# McPiFace-60mmFan-V3.net
KiCad netlist of a schematic drawn in EAGLE
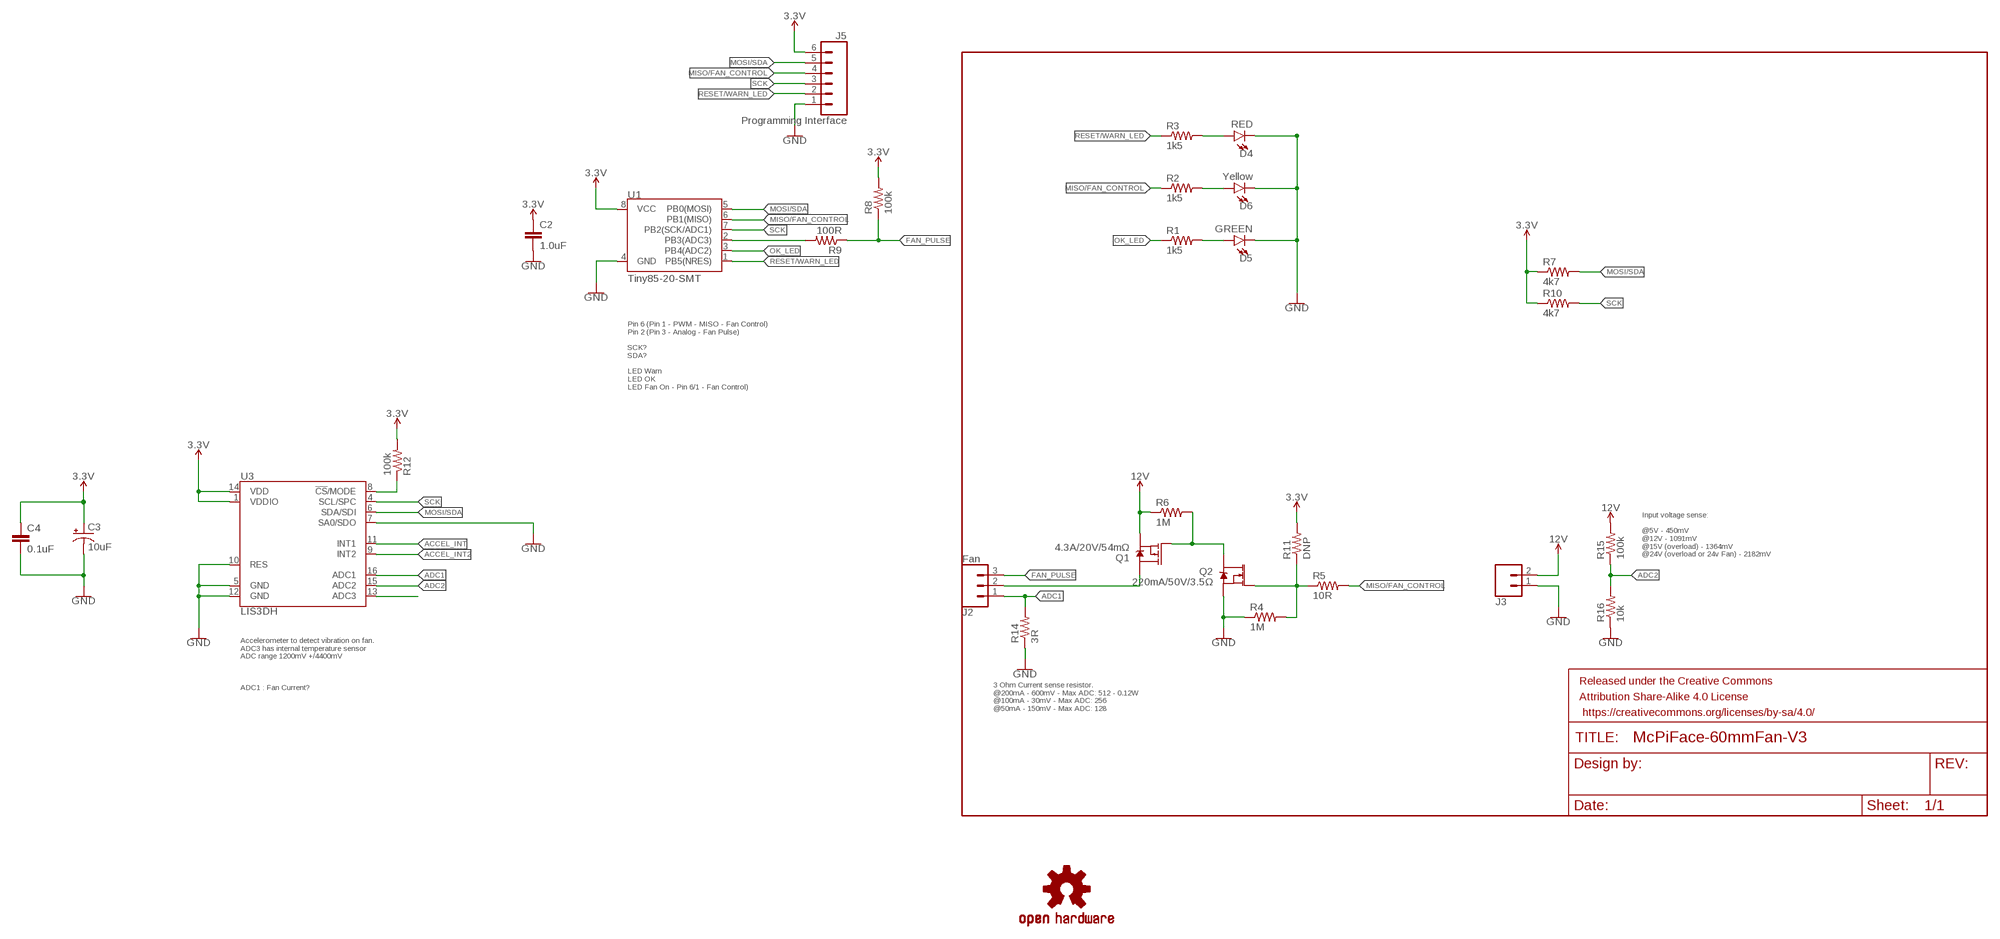
[diagram p0: schematic, sheet 1]

(export (version "E")
  (design (tool "Eeschema 10.0.6"))
  (components
    (comp (ref "C2")
      (value "1.0uF")
      (footprint "eagle-import:0805")
      (libsource (lib "eagle-import") (part "1.0UF-0805-25V-10%"))
    )
    (comp (ref "C3")
      (value "10uF")
      (footprint "eagle-import:EIA3216")
      (libsource (lib "eagle-import") (part "10UF-16V-10%(TANT)"))
    )
    (comp (ref "C4")
      (value "0.1uF")
      (footprint "eagle-import:0805")
      (libsource (lib "eagle-import") (part "1.0UF-0805-25V-10%"))
    )
    (comp (ref "D4")
      (value "RED")
      (footprint "eagle-import:LED-1206")
      (libsource (lib "eagle-import") (part "LED-RED1206"))
    )
    (comp (ref "D5")
      (value "GREEN")
      (footprint "eagle-import:LED-1206")
      (libsource (lib "eagle-import") (part "LED-GREEN1206"))
    )
    (comp (ref "D6")
      (value "Yellow")
      (footprint "eagle-import:LED-1206")
      (libsource (lib "eagle-import") (part "LED-YELLOWLILYPAD"))
    )
    (comp (ref "FRAME1")
      (value "FRAME-LETTER")
      (footprint "eagle-import:CREATIVE_COMMONS")
      (libsource (lib "eagle-import") (part "FRAME-LETTER"))
    )
    (comp (ref "J2")
      (value "Fan")
      (footprint "eagle-import:JST-3-SMD")
      (fields (field (name "MFG") "S3B-PH-SM4-TB(LF)(SN)"))
      (libsource (lib "eagle-import") (part "CONN_03JST-SMD"))
    )
    (comp (ref "J3")
      (value "CONN_02-JST-2MM-SMT")
      (footprint "eagle-import:JST-2-SMD")
      (fields (field (name "MFG") "S2B-PH-SM4-TB(LF)(SN)"))
      (libsource (lib "eagle-import") (part "CONN_02-JST-2MM-SMT"))
    )
    (comp (ref "J5")
      (value "Programming Interface")
      (footprint "eagle-import:1X06-1MM")
      (libsource (lib "eagle-import") (part "CONN_06SMD-1MM"))
    )
    (comp (ref "LOGO1")
      (value "OSHW-LOGOL")
      (footprint "eagle-import:OSHW-LOGO-L")
      (libsource (lib "eagle-import") (part "OSHW-LOGOL"))
    )
    (comp (ref "Q1")
      (value "4.3A/20V/54mΩ")
      (footprint "eagle-import:SOT23-3")
      (libsource (lib "eagle-import") (part "MOSFET_PCH-IRLML2244"))
    )
    (comp (ref "Q2")
      (value "220mA/50V/3.5Ω")
      (footprint "eagle-import:SOT23-3")
      (libsource (lib "eagle-import") (part "MOSFET-NCH-BSS138"))
    )
    (comp (ref "R1")
      (value "1k5")
      (footprint "eagle-import:0805")
      (libsource (lib "eagle-import") (part "RESISTOR0805-RES"))
    )
    (comp (ref "R2")
      (value "1k5")
      (footprint "eagle-import:0805")
      (libsource (lib "eagle-import") (part "RESISTOR0805-RES"))
    )
    (comp (ref "R3")
      (value "1k5")
      (footprint "eagle-import:0805")
      (libsource (lib "eagle-import") (part "RESISTOR0805-RES"))
    )
    (comp (ref "R4")
      (value "1M")
      (footprint "eagle-import:0805")
      (libsource (lib "eagle-import") (part "RESISTOR0805-RES"))
    )
    (comp (ref "R5")
      (value "10R")
      (footprint "eagle-import:0805")
      (libsource (lib "eagle-import") (part "RESISTOR0805-RES"))
    )
    (comp (ref "R6")
      (value "1M")
      (footprint "eagle-import:0805")
      (libsource (lib "eagle-import") (part "RESISTOR0805-RES"))
    )
    (comp (ref "R7")
      (value "4k7")
      (footprint "eagle-import:0805")
      (libsource (lib "eagle-import") (part "RESISTOR0805-RES"))
    )
    (comp (ref "R8")
      (value "100k")
      (footprint "eagle-import:0805")
      (libsource (lib "eagle-import") (part "RESISTOR0805-RES"))
    )
    (comp (ref "R9")
      (value "100R")
      (footprint "eagle-import:0805")
      (libsource (lib "eagle-import") (part "RESISTOR0805-RES"))
    )
    (comp (ref "R10")
      (value "4k7")
      (footprint "eagle-import:0805")
      (libsource (lib "eagle-import") (part "RESISTOR0805-RES"))
    )
    (comp (ref "R11")
      (value "DNP")
      (footprint "eagle-import:0805")
      (libsource (lib "eagle-import") (part "RESISTOR0805-RES"))
    )
    (comp (ref "R12")
      (value "100k")
      (footprint "eagle-import:0805")
      (libsource (lib "eagle-import") (part "RESISTOR0805-RES"))
    )
    (comp (ref "R14")
      (value "3R")
      (footprint "eagle-import:0805")
      (libsource (lib "eagle-import") (part "RESISTOR0805-RES"))
    )
    (comp (ref "R15")
      (value "100k")
      (footprint "eagle-import:0805")
      (libsource (lib "eagle-import") (part "RESISTOR0805-RES"))
    )
    (comp (ref "R16")
      (value "10k")
      (footprint "eagle-import:0805")
      (libsource (lib "eagle-import") (part "RESISTOR0805-RES"))
    )
    (comp (ref "U1")
      (value "Tiny85-20-SMT")
      (footprint "eagle-import:SO08-EIAJ")
      (libsource (lib "eagle-import") (part "ATTINY45TINY85-20-SMT"))
    )
    (comp (ref "U3")
      (value "LIS3DH")
      (footprint "eagle-import:LGA-16-3X3")
      (libsource (lib "eagle-import") (part "LIS3DH"))
    )
  )
  (nets
    (net (code "1") (name "3.3V") (class "Default")
      (node (ref "C2") (pin "1") (pinfunction "1_1") (pintype "passive"))
      (node (ref "C3") (pin "A") (pinfunction "+_A") (pintype "passive"))
      (node (ref "C4") (pin "1") (pinfunction "1_1") (pintype "passive"))
      (node (ref "J5") (pin "6") (pinfunction "6_6") (pintype "passive"))
      (node (ref "R10") (pin "1") (pinfunction "1_1") (pintype "passive"))
      (node (ref "R11") (pin "2") (pinfunction "2_2") (pintype "passive"))
      (node (ref "R12") (pin "2") (pinfunction "2_2") (pintype "passive"))
      (node (ref "R7") (pin "1") (pinfunction "1_1") (pintype "passive"))
      (node (ref "R8") (pin "2") (pinfunction "2_2") (pintype "passive"))
      (node (ref "U1") (pin "8") (pinfunction "VCC_8") (pintype "bidirectional"))
      (node (ref "U3") (pin "1") (pinfunction "VDDIO_1") (pintype "bidirectional"))
      (node (ref "U3") (pin "14") (pinfunction "VDD_14") (pintype "bidirectional"))
    )
    (net (code "2") (name "12V") (class "Default")
      (node (ref "J3") (pin "2") (pinfunction "1_2") (pintype "passive"))
      (node (ref "Q1") (pin "2") (pinfunction "S_2") (pintype "bidirectional"))
      (node (ref "R15") (pin "2") (pinfunction "2_2") (pintype "passive"))
      (node (ref "R6") (pin "1") (pinfunction "1_1") (pintype "passive"))
    )
    (net (code "3") (name "ACCEL_INT") (class "Default")
      (node (ref "U3") (pin "11") (pinfunction "INT1_11") (pintype "bidirectional"))
    )
    (net (code "4") (name "ACCEL_INT2") (class "Default")
      (node (ref "U3") (pin "9") (pinfunction "INT2_9") (pintype "bidirectional"))
    )
    (net (code "5") (name "ADC1") (class "Default")
      (node (ref "J2") (pin "1") (pinfunction "3_1") (pintype "passive"))
      (node (ref "R14") (pin "2") (pinfunction "2_2") (pintype "passive"))
      (node (ref "U3") (pin "16") (pinfunction "ADC1_16") (pintype "bidirectional"))
    )
    (net (code "6") (name "ADC2") (class "Default")
      (node (ref "R15") (pin "1") (pinfunction "1_1") (pintype "passive"))
      (node (ref "R16") (pin "2") (pinfunction "2_2") (pintype "passive"))
      (node (ref "U3") (pin "15") (pinfunction "ADC2_15") (pintype "bidirectional"))
    )
    (net (code "7") (name "FAN_PULSE") (class "Default")
      (node (ref "J2") (pin "3") (pinfunction "1_3") (pintype "passive"))
      (node (ref "R8") (pin "1") (pinfunction "1_1") (pintype "passive"))
      (node (ref "R9") (pin "1") (pinfunction "1_1") (pintype "passive"))
    )
    (net (code "8") (name "GND") (class "Default")
      (node (ref "C2") (pin "2") (pinfunction "2_2") (pintype "passive"))
      (node (ref "C3") (pin "C") (pinfunction "-_C") (pintype "passive"))
      (node (ref "C4") (pin "2") (pinfunction "2_2") (pintype "passive"))
      (node (ref "D4") (pin "C") (pinfunction "C_C") (pintype "passive"))
      (node (ref "D5") (pin "C") (pinfunction "C_C") (pintype "passive"))
      (node (ref "D6") (pin "C") (pinfunction "C_C") (pintype "passive"))
      (node (ref "J3") (pin "1") (pinfunction "2_1") (pintype "passive"))
      (node (ref "J5") (pin "1") (pinfunction "1_1") (pintype "passive"))
      (node (ref "Q2") (pin "2") (pinfunction "S_2") (pintype "bidirectional"))
      (node (ref "R14") (pin "1") (pinfunction "1_1") (pintype "passive"))
      (node (ref "R16") (pin "1") (pinfunction "1_1") (pintype "passive"))
      (node (ref "R4") (pin "1") (pinfunction "1_1") (pintype "passive"))
      (node (ref "U1") (pin "4") (pinfunction "GND_4") (pintype "bidirectional"))
      (node (ref "U3") (pin "10") (pinfunction "RES_10") (pintype "bidirectional"))
      (node (ref "U3") (pin "12") (pinfunction "GND_12") (pintype "bidirectional"))
      (node (ref "U3") (pin "5") (pinfunction "GND_5") (pintype "bidirectional"))
      (node (ref "U3") (pin "7") (pinfunction "SA0/SDO_7") (pintype "bidirectional"))
    )
    (net (code "9") (name "MISO{slash}FAN_CONTROL") (class "Default")
      (node (ref "J5") (pin "4") (pinfunction "4_4") (pintype "passive"))
      (node (ref "R2") (pin "1") (pinfunction "1_1") (pintype "passive"))
      (node (ref "R5") (pin "2") (pinfunction "2_2") (pintype "passive"))
      (node (ref "U1") (pin "6") (pinfunction "PB1(MISO)_6") (pintype "bidirectional"))
    )
    (net (code "10") (name "MOSI{slash}SDA") (class "Default")
      (node (ref "J5") (pin "5") (pinfunction "5_5") (pintype "passive"))
      (node (ref "R7") (pin "2") (pinfunction "2_2") (pintype "passive"))
      (node (ref "U1") (pin "5") (pinfunction "PB0(MOSI)_5") (pintype "bidirectional"))
      (node (ref "U3") (pin "6") (pinfunction "SDA/SDI_6") (pintype "bidirectional"))
    )
    (net (code "11") (name "Net-(D4-PadA)") (class "Default")
      (node (ref "D4") (pin "A") (pinfunction "A_A") (pintype "passive"))
      (node (ref "R3") (pin "2") (pinfunction "2_2") (pintype "passive"))
    )
    (net (code "12") (name "Net-(D5-PadA)") (class "Default")
      (node (ref "D5") (pin "A") (pinfunction "A_A") (pintype "passive"))
      (node (ref "R1") (pin "2") (pinfunction "2_2") (pintype "passive"))
    )
    (net (code "13") (name "Net-(D6-PadA)") (class "Default")
      (node (ref "D6") (pin "A") (pinfunction "A_A") (pintype "passive"))
      (node (ref "R2") (pin "2") (pinfunction "2_2") (pintype "passive"))
    )
    (net (code "14") (name "Net-(Q1-D)") (class "Default")
      (node (ref "J2") (pin "2") (pinfunction "2_2") (pintype "passive"))
      (node (ref "Q1") (pin "3") (pinfunction "D_3") (pintype "bidirectional"))
    )
    (net (code "15") (name "Net-(Q1-G)") (class "Default")
      (node (ref "Q1") (pin "1") (pinfunction "G_1") (pintype "bidirectional"))
      (node (ref "Q2") (pin "3") (pinfunction "D_3") (pintype "bidirectional"))
      (node (ref "R6") (pin "2") (pinfunction "2_2") (pintype "passive"))
    )
    (net (code "16") (name "Net-(Q2-G)") (class "Default")
      (node (ref "Q2") (pin "1") (pinfunction "G_1") (pintype "bidirectional"))
      (node (ref "R11") (pin "1") (pinfunction "1_1") (pintype "passive"))
      (node (ref "R4") (pin "2") (pinfunction "2_2") (pintype "passive"))
      (node (ref "R5") (pin "1") (pinfunction "1_1") (pintype "passive"))
    )
    (net (code "17") (name "Net-(U1-PB3(ADC3))") (class "Default")
      (node (ref "R9") (pin "2") (pinfunction "2_2") (pintype "passive"))
      (node (ref "U1") (pin "2") (pinfunction "PB3(ADC3)_2") (pintype "bidirectional"))
    )
    (net (code "18") (name "Net-(U3-~{CS}{slash}MODE)") (class "Default")
      (node (ref "R12") (pin "1") (pinfunction "1_1") (pintype "passive"))
      (node (ref "U3") (pin "8") (pinfunction "~{CS}/MODE_8") (pintype "bidirectional"))
    )
    (net (code "19") (name "OK_LED") (class "Default")
      (node (ref "R1") (pin "1") (pinfunction "1_1") (pintype "passive"))
      (node (ref "U1") (pin "3") (pinfunction "PB4(ADC2)_3") (pintype "bidirectional"))
    )
    (net (code "20") (name "RESET{slash}WARN_LED") (class "Default")
      (node (ref "J5") (pin "2") (pinfunction "2_2") (pintype "passive"))
      (node (ref "R3") (pin "1") (pinfunction "1_1") (pintype "passive"))
      (node (ref "U1") (pin "1") (pinfunction "PB5(NRES)_1") (pintype "bidirectional"))
    )
    (net (code "21") (name "SCK") (class "Default")
      (node (ref "J5") (pin "3") (pinfunction "3_3") (pintype "passive"))
      (node (ref "R10") (pin "2") (pinfunction "2_2") (pintype "passive"))
      (node (ref "U1") (pin "7") (pinfunction "PB2(SCK/ADC1)_7") (pintype "bidirectional"))
      (node (ref "U3") (pin "4") (pinfunction "SCL/SPC_4") (pintype "bidirectional"))
    )
    (net (code "22") (name "unconnected-(U3-ADC3-Pad13)") (class "Default")
      (node (ref "U3") (pin "13") (pinfunction "ADC3_13") (pintype "bidirectional"))
    )
  )
)
